# circuito.net
KiCad netlist of a schematic drawn in EAGLE
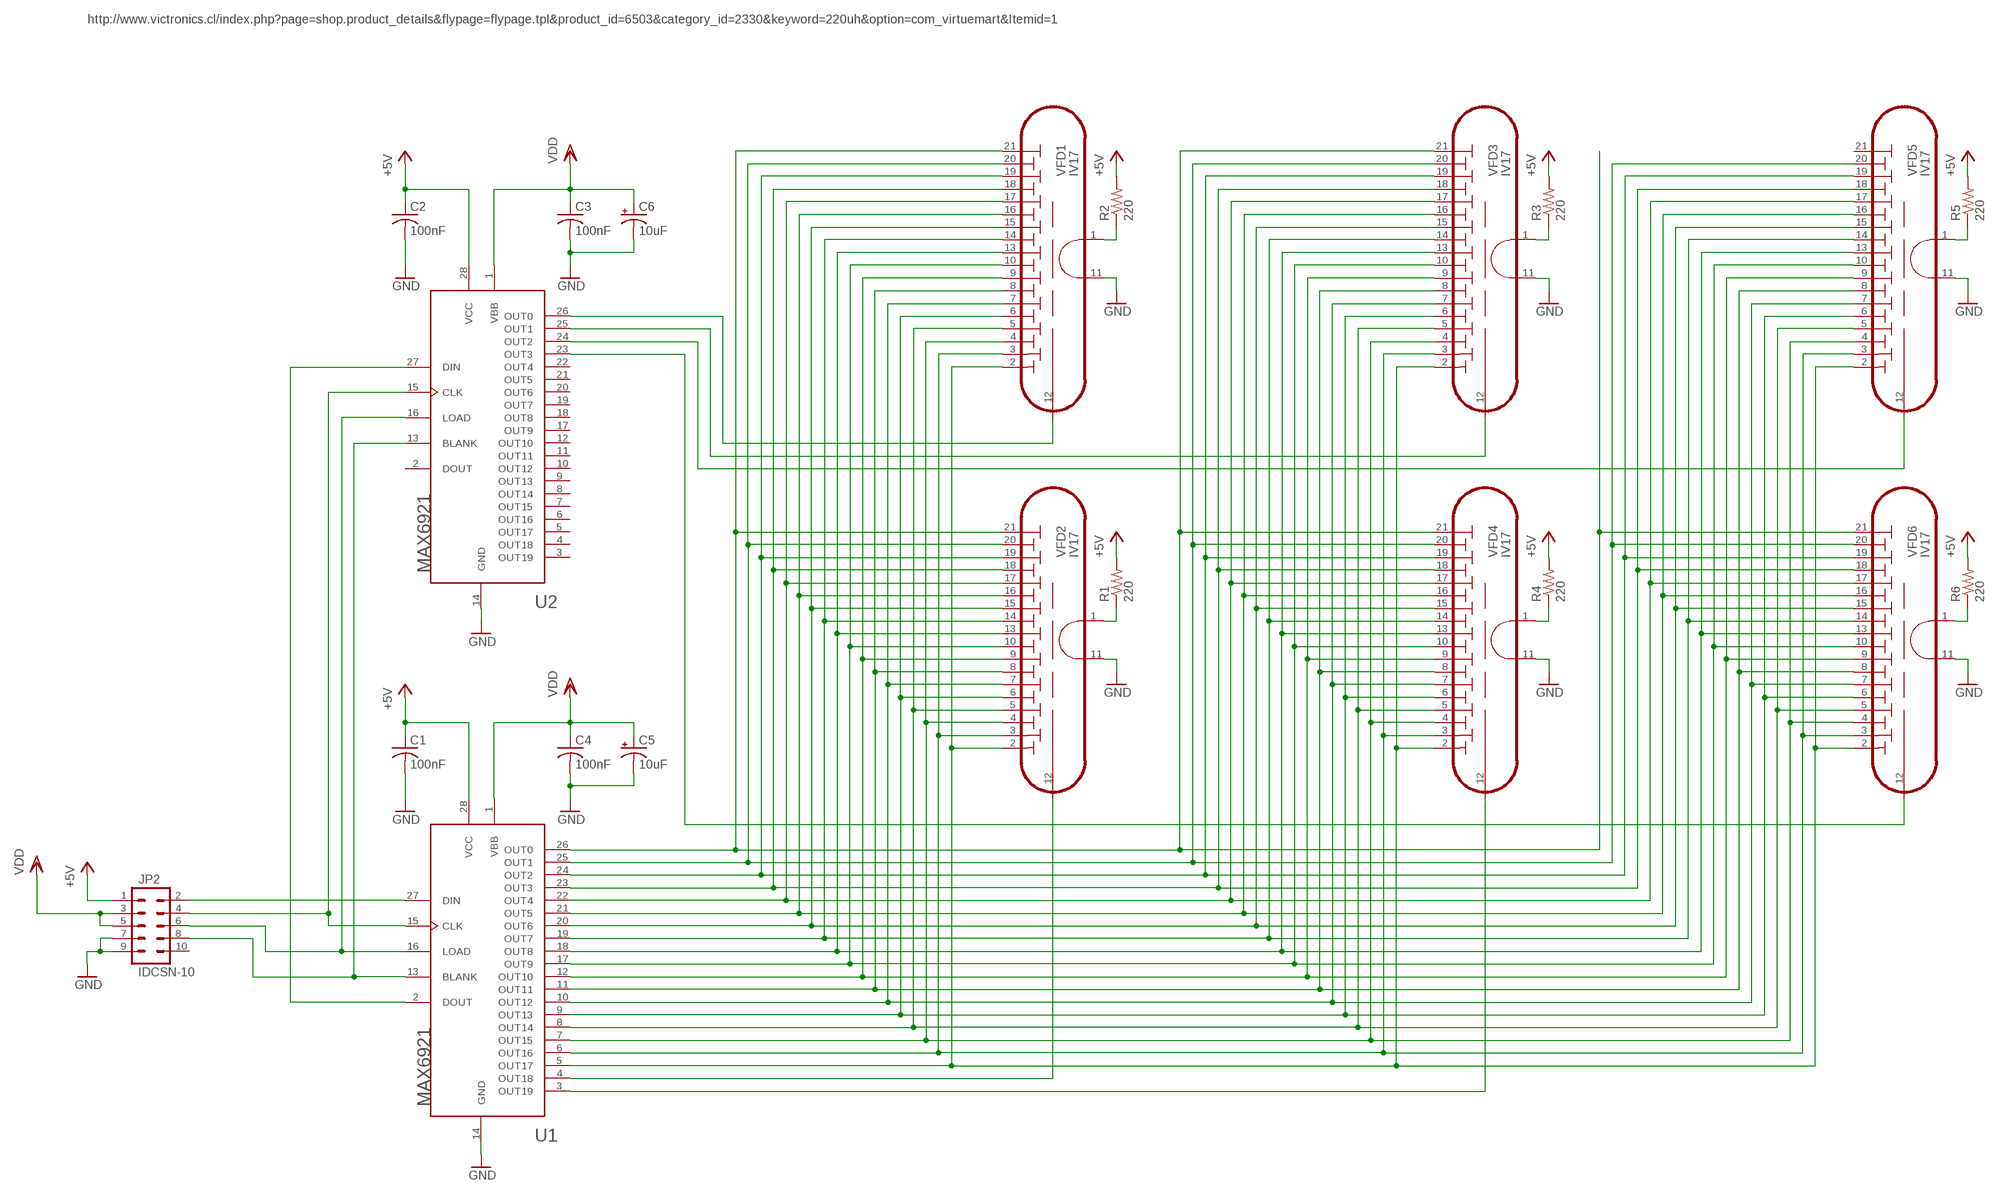
[diagram p0: schematic, sheet 1]

(export (version "E")
  (design (tool "Eeschema 10.0.6"))
  (components
    (comp (ref "C1")
      (value "100nF")
      (footprint "eagle-import:C1206")
      (libsource (lib "eagle-import") (part "C-USC1206"))
    )
    (comp (ref "C2")
      (value "100nF")
      (footprint "eagle-import:C1206")
      (libsource (lib "eagle-import") (part "C-USC1206"))
    )
    (comp (ref "C3")
      (value "100nF")
      (footprint "eagle-import:C1210")
      (libsource (lib "eagle-import") (part "C-USC1210"))
    )
    (comp (ref "C4")
      (value "100nF")
      (footprint "eagle-import:C1210")
      (libsource (lib "eagle-import") (part "C-USC1210"))
    )
    (comp (ref "C5")
      (value "NACEW100M100V6.3X8TR")
      (footprint "eagle-import:NACEW100M100V6.3X8TR")
      (libsource (lib "eagle-import") (part "NACEW100M100V6.3X8TR"))
    )
    (comp (ref "C6")
      (value "NACEW100M100V6.3X8TR")
      (footprint "eagle-import:NACEW100M100V6.3X8TR")
      (libsource (lib "eagle-import") (part "NACEW100M100V6.3X8TR"))
    )
    (comp (ref "JP2")
      (value "IDCSN-10")
      (footprint "eagle-import:IDCSN-10")
      (libsource (lib "eagle-import") (part "IDCSN-10"))
    )
    (comp (ref "R1")
      (value "220")
      (footprint "eagle-import:AXIAL-0.4")
      (libsource (lib "eagle-import") (part "RESISTORPTH-1/4W"))
    )
    (comp (ref "R2")
      (value "220")
      (footprint "eagle-import:AXIAL-0.4")
      (libsource (lib "eagle-import") (part "RESISTORPTH-1/4W"))
    )
    (comp (ref "R3")
      (value "220")
      (footprint "eagle-import:AXIAL-0.4")
      (libsource (lib "eagle-import") (part "RESISTORPTH-1/4W"))
    )
    (comp (ref "R4")
      (value "220")
      (footprint "eagle-import:AXIAL-0.4")
      (libsource (lib "eagle-import") (part "RESISTORPTH-1/4W"))
    )
    (comp (ref "R5")
      (value "220")
      (footprint "eagle-import:AXIAL-0.4")
      (libsource (lib "eagle-import") (part "RESISTORPTH-1/4W"))
    )
    (comp (ref "R6")
      (value "220")
      (footprint "eagle-import:AXIAL-0.4")
      (libsource (lib "eagle-import") (part "RESISTORPTH-1/4W"))
    )
    (comp (ref "U1")
      (value "MAX6921AWI")
      (footprint "eagle-import:SO28W")
      (libsource (lib "eagle-import") (part "MAX6921AWI"))
    )
    (comp (ref "U2")
      (value "MAX6921AWI")
      (footprint "eagle-import:SO28W")
      (libsource (lib "eagle-import") (part "MAX6921AWI"))
    )
    (comp (ref "VFD1")
      (value "IV17")
      (footprint "eagle-import:CIRCULAR")
      (libsource (lib "eagle-import") (part "IV17"))
    )
    (comp (ref "VFD2")
      (value "IV17")
      (footprint "eagle-import:CIRCULAR")
      (libsource (lib "eagle-import") (part "IV17"))
    )
    (comp (ref "VFD3")
      (value "IV17")
      (footprint "eagle-import:CIRCULAR")
      (libsource (lib "eagle-import") (part "IV17"))
    )
    (comp (ref "VFD4")
      (value "IV17")
      (footprint "eagle-import:CIRCULAR")
      (libsource (lib "eagle-import") (part "IV17"))
    )
    (comp (ref "VFD5")
      (value "IV17")
      (footprint "eagle-import:CIRCULAR")
      (libsource (lib "eagle-import") (part "IV17"))
    )
    (comp (ref "VFD6")
      (value "IV17")
      (footprint "eagle-import:CIRCULAR")
      (libsource (lib "eagle-import") (part "IV17"))
    )
  )
  (nets
    (net (code "1") (name "+5V") (class "Default")
      (node (ref "C1") (pin "1") (pinfunction "1_1") (pintype "passive"))
      (node (ref "C2") (pin "1") (pinfunction "1_1") (pintype "passive"))
      (node (ref "JP2") (pin "1") (pinfunction "1_1") (pintype "passive"))
      (node (ref "R1") (pin "P$2") (pinfunction "2_P$2") (pintype "passive"))
      (node (ref "R2") (pin "P$2") (pinfunction "2_P$2") (pintype "passive"))
      (node (ref "R3") (pin "P$2") (pinfunction "2_P$2") (pintype "passive"))
      (node (ref "R4") (pin "P$2") (pinfunction "2_P$2") (pintype "passive"))
      (node (ref "R5") (pin "P$2") (pinfunction "2_P$2") (pintype "passive"))
      (node (ref "R6") (pin "P$2") (pinfunction "2_P$2") (pintype "passive"))
      (node (ref "U1") (pin "28") (pinfunction "VCC_28") (pintype "power_in"))
      (node (ref "U2") (pin "28") (pinfunction "VCC_28") (pintype "power_in"))
    )
    (net (code "2") (name "GND") (class "Default")
      (node (ref "C1") (pin "2") (pinfunction "2_2") (pintype "passive"))
      (node (ref "C2") (pin "2") (pinfunction "2_2") (pintype "passive"))
      (node (ref "C3") (pin "2") (pinfunction "2_2") (pintype "passive"))
      (node (ref "C4") (pin "2") (pinfunction "2_2") (pintype "passive"))
      (node (ref "C5") (pin "NEG") (pinfunction "-_NEG") (pintype "passive"))
      (node (ref "C6") (pin "NEG") (pinfunction "-_NEG") (pintype "passive"))
      (node (ref "JP2") (pin "7") (pinfunction "7_7") (pintype "passive"))
      (node (ref "JP2") (pin "9") (pinfunction "9_9") (pintype "passive"))
      (node (ref "U1") (pin "14") (pinfunction "GND_14") (pintype "power_in"))
      (node (ref "U2") (pin "14") (pinfunction "GND_14") (pintype "power_in"))
      (node (ref "VFD1") (pin "11") (pinfunction "P$11_11") (pintype "bidirectional"))
      (node (ref "VFD2") (pin "11") (pinfunction "P$11_11") (pintype "bidirectional"))
      (node (ref "VFD3") (pin "11") (pinfunction "P$11_11") (pintype "bidirectional"))
      (node (ref "VFD4") (pin "11") (pinfunction "P$11_11") (pintype "bidirectional"))
      (node (ref "VFD5") (pin "11") (pinfunction "P$11_11") (pintype "bidirectional"))
      (node (ref "VFD6") (pin "11") (pinfunction "P$11_11") (pintype "bidirectional"))
    )
    (net (code "3") (name "Net-(R1-1)") (class "Default")
      (node (ref "R1") (pin "P$1") (pinfunction "1_P$1") (pintype "passive"))
      (node (ref "VFD2") (pin "1") (pinfunction "P$1_1") (pintype "bidirectional"))
    )
    (net (code "4") (name "Net-(R2-1)") (class "Default")
      (node (ref "R2") (pin "P$1") (pinfunction "1_P$1") (pintype "passive"))
      (node (ref "VFD1") (pin "1") (pinfunction "P$1_1") (pintype "bidirectional"))
    )
    (net (code "5") (name "Net-(R3-1)") (class "Default")
      (node (ref "R3") (pin "P$1") (pinfunction "1_P$1") (pintype "passive"))
      (node (ref "VFD3") (pin "1") (pinfunction "P$1_1") (pintype "bidirectional"))
    )
    (net (code "6") (name "Net-(R4-1)") (class "Default")
      (node (ref "R4") (pin "P$1") (pinfunction "1_P$1") (pintype "passive"))
      (node (ref "VFD4") (pin "1") (pinfunction "P$1_1") (pintype "bidirectional"))
    )
    (net (code "7") (name "Net-(R5-1)") (class "Default")
      (node (ref "R5") (pin "P$1") (pinfunction "1_P$1") (pintype "passive"))
      (node (ref "VFD5") (pin "1") (pinfunction "P$1_1") (pintype "bidirectional"))
    )
    (net (code "8") (name "Net-(R6-1)") (class "Default")
      (node (ref "R6") (pin "P$1") (pinfunction "1_P$1") (pintype "passive"))
      (node (ref "VFD6") (pin "1") (pinfunction "P$1_1") (pintype "bidirectional"))
    )
    (net (code "9") (name "Net-(U1-BLANK)") (class "Default")
      (node (ref "JP2") (pin "8") (pinfunction "8_8") (pintype "passive"))
      (node (ref "U1") (pin "13") (pinfunction "BLANK_13") (pintype "input"))
      (node (ref "U2") (pin "13") (pinfunction "BLANK_13") (pintype "input"))
    )
    (net (code "10") (name "Net-(U1-CLK)") (class "Default")
      (node (ref "JP2") (pin "4") (pinfunction "4_4") (pintype "passive"))
      (node (ref "U1") (pin "15") (pinfunction "CLK_15") (pintype "input"))
      (node (ref "U2") (pin "15") (pinfunction "CLK_15") (pintype "input"))
    )
    (net (code "11") (name "Net-(U1-DIN)") (class "Default")
      (node (ref "JP2") (pin "2") (pinfunction "2_2") (pintype "passive"))
      (node (ref "U1") (pin "27") (pinfunction "DIN_27") (pintype "input"))
    )
    (net (code "12") (name "Net-(U1-DOUT)") (class "Default")
      (node (ref "U1") (pin "2") (pinfunction "DOUT_2") (pintype "output"))
      (node (ref "U2") (pin "27") (pinfunction "DIN_27") (pintype "input"))
    )
    (net (code "13") (name "Net-(U1-LOAD)") (class "Default")
      (node (ref "JP2") (pin "6") (pinfunction "6_6") (pintype "passive"))
      (node (ref "U1") (pin "16") (pinfunction "LOAD_16") (pintype "input"))
      (node (ref "U2") (pin "16") (pinfunction "LOAD_16") (pintype "input"))
    )
    (net (code "14") (name "Net-(U1-OUT0)") (class "Default")
      (node (ref "U1") (pin "26") (pinfunction "OUT0_26") (pintype "output"))
      (node (ref "VFD1") (pin "21") (pinfunction "P$21_21") (pintype "input"))
      (node (ref "VFD2") (pin "21") (pinfunction "P$21_21") (pintype "input"))
      (node (ref "VFD3") (pin "21") (pinfunction "P$21_21") (pintype "input"))
      (node (ref "VFD4") (pin "21") (pinfunction "P$21_21") (pintype "input"))
      (node (ref "VFD6") (pin "21") (pinfunction "P$21_21") (pintype "input"))
    )
    (net (code "15") (name "Net-(U1-OUT1)") (class "Default")
      (node (ref "U1") (pin "25") (pinfunction "OUT1_25") (pintype "output"))
      (node (ref "VFD1") (pin "20") (pinfunction "P$20_20") (pintype "input"))
      (node (ref "VFD2") (pin "20") (pinfunction "P$20_20") (pintype "input"))
      (node (ref "VFD3") (pin "20") (pinfunction "P$20_20") (pintype "input"))
      (node (ref "VFD4") (pin "20") (pinfunction "P$20_20") (pintype "input"))
      (node (ref "VFD5") (pin "20") (pinfunction "P$20_20") (pintype "input"))
      (node (ref "VFD6") (pin "20") (pinfunction "P$20_20") (pintype "input"))
    )
    (net (code "16") (name "Net-(U1-OUT2)") (class "Default")
      (node (ref "U1") (pin "24") (pinfunction "OUT2_24") (pintype "output"))
      (node (ref "VFD1") (pin "19") (pinfunction "P$19_19") (pintype "input"))
      (node (ref "VFD2") (pin "19") (pinfunction "P$19_19") (pintype "input"))
      (node (ref "VFD3") (pin "19") (pinfunction "P$19_19") (pintype "input"))
      (node (ref "VFD4") (pin "19") (pinfunction "P$19_19") (pintype "input"))
      (node (ref "VFD5") (pin "19") (pinfunction "P$19_19") (pintype "input"))
      (node (ref "VFD6") (pin "19") (pinfunction "P$19_19") (pintype "input"))
    )
    (net (code "17") (name "Net-(U1-OUT3)") (class "Default")
      (node (ref "U1") (pin "23") (pinfunction "OUT3_23") (pintype "output"))
      (node (ref "VFD1") (pin "18") (pinfunction "P$18_18") (pintype "input"))
      (node (ref "VFD2") (pin "18") (pinfunction "P$18_18") (pintype "input"))
      (node (ref "VFD3") (pin "18") (pinfunction "P$18_18") (pintype "input"))
      (node (ref "VFD4") (pin "18") (pinfunction "P$18_18") (pintype "input"))
      (node (ref "VFD5") (pin "18") (pinfunction "P$18_18") (pintype "input"))
      (node (ref "VFD6") (pin "18") (pinfunction "P$18_18") (pintype "input"))
    )
    (net (code "18") (name "Net-(U1-OUT4)") (class "Default")
      (node (ref "U1") (pin "22") (pinfunction "OUT4_22") (pintype "output"))
      (node (ref "VFD1") (pin "17") (pinfunction "P$17_17") (pintype "input"))
      (node (ref "VFD2") (pin "17") (pinfunction "P$17_17") (pintype "input"))
      (node (ref "VFD3") (pin "17") (pinfunction "P$17_17") (pintype "input"))
      (node (ref "VFD4") (pin "17") (pinfunction "P$17_17") (pintype "input"))
      (node (ref "VFD5") (pin "17") (pinfunction "P$17_17") (pintype "input"))
      (node (ref "VFD6") (pin "17") (pinfunction "P$17_17") (pintype "input"))
    )
    (net (code "19") (name "Net-(U1-OUT5)") (class "Default")
      (node (ref "U1") (pin "21") (pinfunction "OUT5_21") (pintype "output"))
      (node (ref "VFD1") (pin "16") (pinfunction "P$16_16") (pintype "input"))
      (node (ref "VFD2") (pin "16") (pinfunction "P$16_16") (pintype "input"))
      (node (ref "VFD3") (pin "16") (pinfunction "P$16_16") (pintype "input"))
      (node (ref "VFD4") (pin "16") (pinfunction "P$16_16") (pintype "input"))
      (node (ref "VFD5") (pin "16") (pinfunction "P$16_16") (pintype "input"))
      (node (ref "VFD6") (pin "16") (pinfunction "P$16_16") (pintype "input"))
    )
    (net (code "20") (name "Net-(U1-OUT6)") (class "Default")
      (node (ref "U1") (pin "20") (pinfunction "OUT6_20") (pintype "output"))
      (node (ref "VFD1") (pin "15") (pinfunction "P$15_15") (pintype "input"))
      (node (ref "VFD2") (pin "15") (pinfunction "P$15_15") (pintype "input"))
      (node (ref "VFD3") (pin "15") (pinfunction "P$15_15") (pintype "input"))
      (node (ref "VFD4") (pin "15") (pinfunction "P$15_15") (pintype "input"))
      (node (ref "VFD5") (pin "15") (pinfunction "P$15_15") (pintype "input"))
      (node (ref "VFD6") (pin "15") (pinfunction "P$15_15") (pintype "input"))
    )
    (net (code "21") (name "Net-(U1-OUT7)") (class "Default")
      (node (ref "U1") (pin "19") (pinfunction "OUT7_19") (pintype "output"))
      (node (ref "VFD1") (pin "14") (pinfunction "P$14_14") (pintype "input"))
      (node (ref "VFD2") (pin "14") (pinfunction "P$14_14") (pintype "input"))
      (node (ref "VFD3") (pin "14") (pinfunction "P$14_14") (pintype "input"))
      (node (ref "VFD4") (pin "14") (pinfunction "P$14_14") (pintype "input"))
      (node (ref "VFD5") (pin "14") (pinfunction "P$14_14") (pintype "input"))
      (node (ref "VFD6") (pin "14") (pinfunction "P$14_14") (pintype "input"))
    )
    (net (code "22") (name "Net-(U1-OUT8)") (class "Default")
      (node (ref "U1") (pin "18") (pinfunction "OUT8_18") (pintype "output"))
      (node (ref "VFD1") (pin "13") (pinfunction "P$13_13") (pintype "input"))
      (node (ref "VFD2") (pin "13") (pinfunction "P$13_13") (pintype "input"))
      (node (ref "VFD3") (pin "13") (pinfunction "P$13_13") (pintype "input"))
      (node (ref "VFD4") (pin "13") (pinfunction "P$13_13") (pintype "input"))
      (node (ref "VFD5") (pin "13") (pinfunction "P$13_13") (pintype "input"))
      (node (ref "VFD6") (pin "13") (pinfunction "P$13_13") (pintype "input"))
    )
    (net (code "23") (name "Net-(U1-OUT9)") (class "Default")
      (node (ref "U1") (pin "17") (pinfunction "OUT9_17") (pintype "output"))
      (node (ref "VFD1") (pin "10") (pinfunction "P$10_10") (pintype "input"))
      (node (ref "VFD2") (pin "10") (pinfunction "P$10_10") (pintype "input"))
      (node (ref "VFD3") (pin "10") (pinfunction "P$10_10") (pintype "input"))
      (node (ref "VFD4") (pin "10") (pinfunction "P$10_10") (pintype "input"))
      (node (ref "VFD5") (pin "10") (pinfunction "P$10_10") (pintype "input"))
      (node (ref "VFD6") (pin "10") (pinfunction "P$10_10") (pintype "input"))
    )
    (net (code "24") (name "Net-(U1-OUT10)") (class "Default")
      (node (ref "U1") (pin "12") (pinfunction "OUT10_12") (pintype "output"))
      (node (ref "VFD1") (pin "9") (pinfunction "P$9_9") (pintype "input"))
      (node (ref "VFD2") (pin "9") (pinfunction "P$9_9") (pintype "input"))
      (node (ref "VFD3") (pin "9") (pinfunction "P$9_9") (pintype "input"))
      (node (ref "VFD4") (pin "9") (pinfunction "P$9_9") (pintype "input"))
      (node (ref "VFD5") (pin "9") (pinfunction "P$9_9") (pintype "input"))
      (node (ref "VFD6") (pin "9") (pinfunction "P$9_9") (pintype "input"))
    )
    (net (code "25") (name "Net-(U1-OUT11)") (class "Default")
      (node (ref "U1") (pin "11") (pinfunction "OUT11_11") (pintype "output"))
      (node (ref "VFD1") (pin "8") (pinfunction "P$8_8") (pintype "input"))
      (node (ref "VFD2") (pin "8") (pinfunction "P$8_8") (pintype "input"))
      (node (ref "VFD3") (pin "8") (pinfunction "P$8_8") (pintype "input"))
      (node (ref "VFD4") (pin "8") (pinfunction "P$8_8") (pintype "input"))
      (node (ref "VFD5") (pin "8") (pinfunction "P$8_8") (pintype "input"))
      (node (ref "VFD6") (pin "8") (pinfunction "P$8_8") (pintype "input"))
    )
    (net (code "26") (name "Net-(U1-OUT12)") (class "Default")
      (node (ref "U1") (pin "10") (pinfunction "OUT12_10") (pintype "output"))
      (node (ref "VFD1") (pin "7") (pinfunction "P$7_7") (pintype "input"))
      (node (ref "VFD2") (pin "7") (pinfunction "P$7_7") (pintype "input"))
      (node (ref "VFD3") (pin "7") (pinfunction "P$7_7") (pintype "input"))
      (node (ref "VFD4") (pin "7") (pinfunction "P$7_7") (pintype "input"))
      (node (ref "VFD5") (pin "7") (pinfunction "P$7_7") (pintype "input"))
      (node (ref "VFD6") (pin "7") (pinfunction "P$7_7") (pintype "input"))
    )
    (net (code "27") (name "Net-(U1-OUT13)") (class "Default")
      (node (ref "U1") (pin "9") (pinfunction "OUT13_9") (pintype "output"))
      (node (ref "VFD1") (pin "6") (pinfunction "P$6_6") (pintype "input"))
      (node (ref "VFD2") (pin "6") (pinfunction "P$6_6") (pintype "input"))
      (node (ref "VFD3") (pin "6") (pinfunction "P$6_6") (pintype "input"))
      (node (ref "VFD4") (pin "6") (pinfunction "P$6_6") (pintype "input"))
      (node (ref "VFD5") (pin "6") (pinfunction "P$6_6") (pintype "input"))
      (node (ref "VFD6") (pin "6") (pinfunction "P$6_6") (pintype "input"))
    )
    (net (code "28") (name "Net-(U1-OUT14)") (class "Default")
      (node (ref "U1") (pin "8") (pinfunction "OUT14_8") (pintype "output"))
      (node (ref "VFD1") (pin "5") (pinfunction "P$5_5") (pintype "input"))
      (node (ref "VFD2") (pin "5") (pinfunction "P$5_5") (pintype "input"))
      (node (ref "VFD3") (pin "5") (pinfunction "P$5_5") (pintype "input"))
      (node (ref "VFD4") (pin "5") (pinfunction "P$5_5") (pintype "input"))
      (node (ref "VFD5") (pin "5") (pinfunction "P$5_5") (pintype "input"))
      (node (ref "VFD6") (pin "5") (pinfunction "P$5_5") (pintype "input"))
    )
    (net (code "29") (name "Net-(U1-OUT15)") (class "Default")
      (node (ref "U1") (pin "7") (pinfunction "OUT15_7") (pintype "output"))
      (node (ref "VFD1") (pin "4") (pinfunction "P$4_4") (pintype "input"))
      (node (ref "VFD2") (pin "4") (pinfunction "P$4_4") (pintype "input"))
      (node (ref "VFD3") (pin "4") (pinfunction "P$4_4") (pintype "input"))
      (node (ref "VFD4") (pin "4") (pinfunction "P$4_4") (pintype "input"))
      (node (ref "VFD5") (pin "4") (pinfunction "P$4_4") (pintype "input"))
      (node (ref "VFD6") (pin "4") (pinfunction "P$4_4") (pintype "input"))
    )
    (net (code "30") (name "Net-(U1-OUT16)") (class "Default")
      (node (ref "U1") (pin "6") (pinfunction "OUT16_6") (pintype "output"))
      (node (ref "VFD1") (pin "3") (pinfunction "P$3_3") (pintype "input"))
      (node (ref "VFD2") (pin "3") (pinfunction "P$3_3") (pintype "input"))
      (node (ref "VFD3") (pin "3") (pinfunction "P$3_3") (pintype "input"))
      (node (ref "VFD4") (pin "3") (pinfunction "P$3_3") (pintype "input"))
      (node (ref "VFD5") (pin "3") (pinfunction "P$3_3") (pintype "input"))
      (node (ref "VFD6") (pin "3") (pinfunction "P$3_3") (pintype "input"))
    )
    (net (code "31") (name "Net-(U1-OUT17)") (class "Default")
      (node (ref "U1") (pin "5") (pinfunction "OUT17_5") (pintype "output"))
      (node (ref "VFD1") (pin "2") (pinfunction "P$2_2") (pintype "input"))
      (node (ref "VFD2") (pin "2") (pinfunction "P$2_2") (pintype "input"))
      (node (ref "VFD3") (pin "2") (pinfunction "P$2_2") (pintype "input"))
      (node (ref "VFD4") (pin "2") (pinfunction "P$2_2") (pintype "input"))
      (node (ref "VFD5") (pin "2") (pinfunction "P$2_2") (pintype "input"))
      (node (ref "VFD6") (pin "2") (pinfunction "P$2_2") (pintype "input"))
    )
    (net (code "32") (name "Net-(U1-OUT18)") (class "Default")
      (node (ref "U1") (pin "4") (pinfunction "OUT18_4") (pintype "output"))
      (node (ref "VFD2") (pin "12") (pinfunction "P$12_12") (pintype "input"))
    )
    (net (code "33") (name "Net-(U1-OUT19)") (class "Default")
      (node (ref "U1") (pin "3") (pinfunction "OUT19_3") (pintype "output"))
      (node (ref "VFD4") (pin "12") (pinfunction "P$12_12") (pintype "input"))
    )
    (net (code "34") (name "Net-(U2-OUT0)") (class "Default")
      (node (ref "U2") (pin "26") (pinfunction "OUT0_26") (pintype "output"))
      (node (ref "VFD1") (pin "12") (pinfunction "P$12_12") (pintype "input"))
    )
    (net (code "35") (name "Net-(U2-OUT1)") (class "Default")
      (node (ref "U2") (pin "25") (pinfunction "OUT1_25") (pintype "output"))
      (node (ref "VFD3") (pin "12") (pinfunction "P$12_12") (pintype "input"))
    )
    (net (code "36") (name "Net-(U2-OUT2)") (class "Default")
      (node (ref "U2") (pin "24") (pinfunction "OUT2_24") (pintype "output"))
      (node (ref "VFD5") (pin "12") (pinfunction "P$12_12") (pintype "input"))
    )
    (net (code "37") (name "Net-(U2-OUT3)") (class "Default")
      (node (ref "U2") (pin "23") (pinfunction "OUT3_23") (pintype "output"))
      (node (ref "VFD6") (pin "12") (pinfunction "P$12_12") (pintype "input"))
    )
    (net (code "38") (name "VDD") (class "Default")
      (node (ref "C3") (pin "1") (pinfunction "1_1") (pintype "passive"))
      (node (ref "C4") (pin "1") (pinfunction "1_1") (pintype "passive"))
      (node (ref "C5") (pin "POS") (pinfunction "+_POS") (pintype "passive"))
      (node (ref "C6") (pin "POS") (pinfunction "+_POS") (pintype "passive"))
      (node (ref "JP2") (pin "3") (pinfunction "3_3") (pintype "passive"))
      (node (ref "JP2") (pin "5") (pinfunction "5_5") (pintype "passive"))
      (node (ref "U1") (pin "1") (pinfunction "VBB_1") (pintype "power_in"))
      (node (ref "U2") (pin "1") (pinfunction "VBB_1") (pintype "power_in"))
    )
    (net (code "39") (name "unconnected-(JP2-Pad10)") (class "Default")
      (node (ref "JP2") (pin "10") (pinfunction "10_10") (pintype "passive"))
    )
    (net (code "40") (name "unconnected-(U2-DOUT-Pad2)") (class "Default")
      (node (ref "U2") (pin "2") (pinfunction "DOUT_2") (pintype "output"))
    )
    (net (code "41") (name "unconnected-(U2-OUT4-Pad22)") (class "Default")
      (node (ref "U2") (pin "22") (pinfunction "OUT4_22") (pintype "output"))
    )
    (net (code "42") (name "unconnected-(U2-OUT5-Pad21)") (class "Default")
      (node (ref "U2") (pin "21") (pinfunction "OUT5_21") (pintype "output"))
    )
    (net (code "43") (name "unconnected-(U2-OUT6-Pad20)") (class "Default")
      (node (ref "U2") (pin "20") (pinfunction "OUT6_20") (pintype "output"))
    )
    (net (code "44") (name "unconnected-(U2-OUT7-Pad19)") (class "Default")
      (node (ref "U2") (pin "19") (pinfunction "OUT7_19") (pintype "output"))
    )
    (net (code "45") (name "unconnected-(U2-OUT8-Pad18)") (class "Default")
      (node (ref "U2") (pin "18") (pinfunction "OUT8_18") (pintype "output"))
    )
    (net (code "46") (name "unconnected-(U2-OUT9-Pad17)") (class "Default")
      (node (ref "U2") (pin "17") (pinfunction "OUT9_17") (pintype "output"))
    )
    (net (code "47") (name "unconnected-(U2-OUT10-Pad12)") (class "Default")
      (node (ref "U2") (pin "12") (pinfunction "OUT10_12") (pintype "output"))
    )
    (net (code "48") (name "unconnected-(U2-OUT11-Pad11)") (class "Default")
      (node (ref "U2") (pin "11") (pinfunction "OUT11_11") (pintype "output"))
    )
    (net (code "49") (name "unconnected-(U2-OUT12-Pad10)") (class "Default")
      (node (ref "U2") (pin "10") (pinfunction "OUT12_10") (pintype "output"))
    )
    (net (code "50") (name "unconnected-(U2-OUT13-Pad9)") (class "Default")
      (node (ref "U2") (pin "9") (pinfunction "OUT13_9") (pintype "output"))
    )
    (net (code "51") (name "unconnected-(U2-OUT14-Pad8)") (class "Default")
      (node (ref "U2") (pin "8") (pinfunction "OUT14_8") (pintype "output"))
    )
    (net (code "52") (name "unconnected-(U2-OUT15-Pad7)") (class "Default")
      (node (ref "U2") (pin "7") (pinfunction "OUT15_7") (pintype "output"))
    )
    (net (code "53") (name "unconnected-(U2-OUT16-Pad6)") (class "Default")
      (node (ref "U2") (pin "6") (pinfunction "OUT16_6") (pintype "output"))
    )
    (net (code "54") (name "unconnected-(U2-OUT17-Pad5)") (class "Default")
      (node (ref "U2") (pin "5") (pinfunction "OUT17_5") (pintype "output"))
    )
    (net (code "55") (name "unconnected-(U2-OUT18-Pad4)") (class "Default")
      (node (ref "U2") (pin "4") (pinfunction "OUT18_4") (pintype "output"))
    )
    (net (code "56") (name "unconnected-(U2-OUT19-Pad3)") (class "Default")
      (node (ref "U2") (pin "3") (pinfunction "OUT19_3") (pintype "output"))
    )
    (net (code "57") (name "unconnected-(VFD5-P$21-Pad21)") (class "Default")
      (node (ref "VFD5") (pin "21") (pinfunction "P$21_21") (pintype "input"))
    )
  )
)
